# ch340_civ.net
KiCad netlist of a schematic drawn in EAGLE
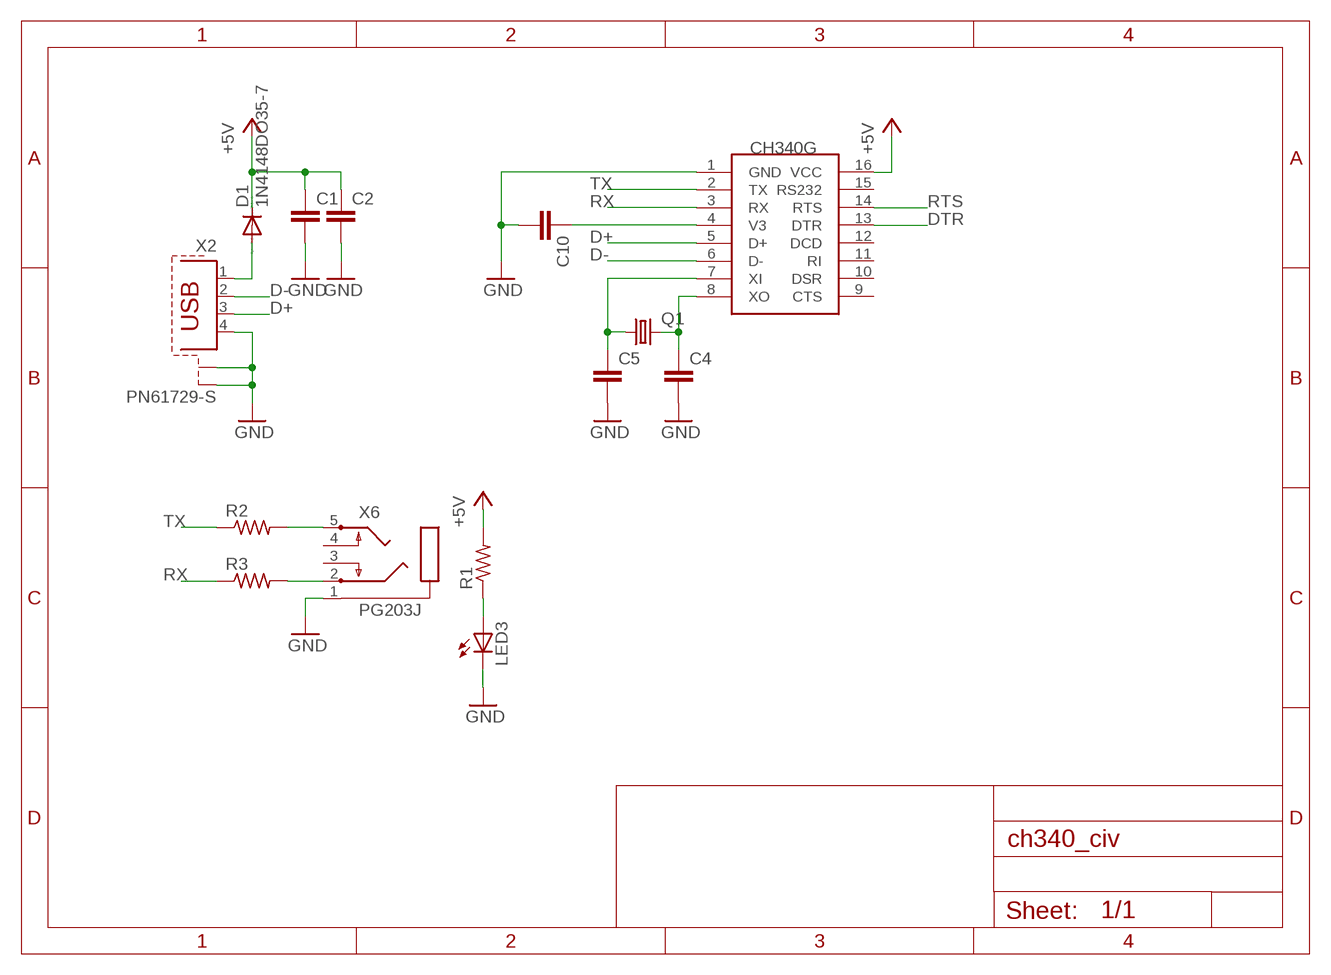
[diagram p0: schematic, sheet 1]

(export (version "E")
  (design (tool "Eeschema 10.0.6"))
  (components
    (comp (ref "C1")
      (value "C-EUC0805K")
      (footprint "eagle-import:C0805K")
      (libsource (lib "eagle-import") (part "C-EUC0805K"))
    )
    (comp (ref "C2")
      (value "C-EUC0805K")
      (footprint "eagle-import:C0805K")
      (libsource (lib "eagle-import") (part "C-EUC0805K"))
    )
    (comp (ref "C4")
      (value "C-EUC0805K")
      (footprint "eagle-import:C0805K")
      (libsource (lib "eagle-import") (part "C-EUC0805K"))
    )
    (comp (ref "C5")
      (value "C-EUC0805K")
      (footprint "eagle-import:C0805K")
      (libsource (lib "eagle-import") (part "C-EUC0805K"))
    )
    (comp (ref "C10")
      (value "C-EUC0805K")
      (footprint "eagle-import:C0805K")
      (libsource (lib "eagle-import") (part "C-EUC0805K"))
    )
    (comp (ref "D1")
      (value "1N4148DO35-7")
      (footprint "eagle-import:DO35-7")
      (libsource (lib "eagle-import") (part "1N4148DO35-7"))
    )
    (comp (ref "LED3")
      (value "LED3MM")
      (footprint "eagle-import:LED3MM")
      (libsource (lib "eagle-import") (part "LED3MM"))
    )
    (comp (ref "Q1")
      (value "CRYSTALHC49S")
      (footprint "eagle-import:HC49_S")
      (libsource (lib "eagle-import") (part "CRYSTALHC49S"))
    )
    (comp (ref "R1")
      (value "R-US_R0805")
      (footprint "eagle-import:R0805")
      (libsource (lib "eagle-import") (part "R-US_R0805"))
    )
    (comp (ref "R2")
      (value "R-US_M0805")
      (footprint "eagle-import:M0805")
      (libsource (lib "eagle-import") (part "R-US_M0805"))
    )
    (comp (ref "R3")
      (value "R-US_M0805")
      (footprint "eagle-import:M0805")
      (libsource (lib "eagle-import") (part "R-US_M0805"))
    )
    (comp (ref "U$1")
      (value "CH340G")
      (footprint "eagle-import:SOIC16")
      (libsource (lib "eagle-import") (part "CH340G"))
    )
    (comp (ref "X2")
      (value "PN61729-S")
      (footprint "eagle-import:PN61729-S")
      (libsource (lib "eagle-import") (part "PN61729-S"))
    )
    (comp (ref "X6")
      (value "PG203J")
      (footprint "eagle-import:PG203J")
      (libsource (lib "eagle-import") (part "PG203J"))
    )
  )
  (nets
    (net (code "1") (name "+5V") (class "Default")
      (node (ref "C1") (pin "1") (pinfunction "1_1") (pintype "passive"))
      (node (ref "C2") (pin "1") (pinfunction "1_1") (pintype "passive"))
      (node (ref "D1") (pin "C") (pinfunction "C_C") (pintype "passive"))
      (node (ref "R1") (pin "2") (pinfunction "2_2") (pintype "passive"))
      (node (ref "U$1") (pin "16") (pinfunction "VCC_16") (pintype "bidirectional"))
    )
    (net (code "2") (name "/D+") (class "Default")
      (node (ref "U$1") (pin "5") (pinfunction "D+_5") (pintype "bidirectional"))
      (node (ref "X2") (pin "3") (pinfunction "3_3") (pintype "passive"))
    )
    (net (code "3") (name "/D-") (class "Default")
      (node (ref "U$1") (pin "6") (pinfunction "D-_6") (pintype "bidirectional"))
      (node (ref "X2") (pin "2") (pinfunction "2_2") (pintype "passive"))
    )
    (net (code "4") (name "/DTR") (class "Default")
      (node (ref "U$1") (pin "13") (pinfunction "DTR_13") (pintype "bidirectional"))
    )
    (net (code "5") (name "/RTS") (class "Default")
      (node (ref "U$1") (pin "14") (pinfunction "RTS_14") (pintype "bidirectional"))
    )
    (net (code "6") (name "/RX") (class "Default")
      (node (ref "R3") (pin "1") (pinfunction "1_1") (pintype "passive"))
      (node (ref "U$1") (pin "3") (pinfunction "RX_3") (pintype "bidirectional"))
    )
    (net (code "7") (name "/TX") (class "Default")
      (node (ref "R2") (pin "1") (pinfunction "1_1") (pintype "passive"))
      (node (ref "U$1") (pin "2") (pinfunction "TX_2") (pintype "bidirectional"))
    )
    (net (code "8") (name "GND") (class "Default")
      (node (ref "C1") (pin "2") (pinfunction "2_2") (pintype "passive"))
      (node (ref "C10") (pin "2") (pinfunction "2_2") (pintype "passive"))
      (node (ref "C2") (pin "2") (pinfunction "2_2") (pintype "passive"))
      (node (ref "C4") (pin "2") (pinfunction "2_2") (pintype "passive"))
      (node (ref "C5") (pin "2") (pinfunction "2_2") (pintype "passive"))
      (node (ref "LED3") (pin "K") (pinfunction "C_K") (pintype "passive"))
      (node (ref "U$1") (pin "1") (pinfunction "GND_1") (pintype "bidirectional"))
      (node (ref "X2") (pin "4") (pinfunction "4_4") (pintype "passive"))
      (node (ref "X2") (pin "S1") (pinfunction "S1_S1") (pintype "passive"))
      (node (ref "X2") (pin "S2") (pinfunction "S2_S2") (pintype "passive"))
      (node (ref "X6") (pin "1") (pinfunction "1_1") (pintype "passive"))
    )
    (net (code "9") (name "Net-(D1-PadA)") (class "Default")
      (node (ref "D1") (pin "A") (pinfunction "A_A") (pintype "passive"))
      (node (ref "X2") (pin "1") (pinfunction "1_1") (pintype "passive"))
    )
    (net (code "10") (name "Net-(LED3-PadA)") (class "Default")
      (node (ref "LED3") (pin "A") (pinfunction "A_A") (pintype "passive"))
      (node (ref "R1") (pin "1") (pinfunction "1_1") (pintype "passive"))
    )
    (net (code "11") (name "Net-(R2-Pad2)") (class "Default")
      (node (ref "R2") (pin "2") (pinfunction "2_2") (pintype "passive"))
      (node (ref "X6") (pin "5") (pinfunction "5_5") (pintype "passive"))
    )
    (net (code "12") (name "Net-(R3-Pad2)") (class "Default")
      (node (ref "R3") (pin "2") (pinfunction "2_2") (pintype "passive"))
      (node (ref "X6") (pin "2") (pinfunction "2_2") (pintype "passive"))
    )
    (net (code "13") (name "Net-(U$1-V3)") (class "Default")
      (node (ref "C10") (pin "1") (pinfunction "1_1") (pintype "passive"))
      (node (ref "U$1") (pin "4") (pinfunction "V3_4") (pintype "bidirectional"))
    )
    (net (code "14") (name "Net-(U$1-XI)") (class "Default")
      (node (ref "C5") (pin "1") (pinfunction "1_1") (pintype "passive"))
      (node (ref "Q1") (pin "1") (pinfunction "1_1") (pintype "passive"))
      (node (ref "U$1") (pin "7") (pinfunction "XI_7") (pintype "bidirectional"))
    )
    (net (code "15") (name "Net-(U$1-XO)") (class "Default")
      (node (ref "C4") (pin "1") (pinfunction "1_1") (pintype "passive"))
      (node (ref "Q1") (pin "2") (pinfunction "2_2") (pintype "passive"))
      (node (ref "U$1") (pin "8") (pinfunction "XO_8") (pintype "bidirectional"))
    )
    (net (code "16") (name "unconnected-(U$1-CTS-Pad9)") (class "Default")
      (node (ref "U$1") (pin "9") (pinfunction "CTS_9") (pintype "bidirectional"))
    )
    (net (code "17") (name "unconnected-(U$1-DCD-Pad12)") (class "Default")
      (node (ref "U$1") (pin "12") (pinfunction "DCD_12") (pintype "bidirectional"))
    )
    (net (code "18") (name "unconnected-(U$1-DSR-Pad10)") (class "Default")
      (node (ref "U$1") (pin "10") (pinfunction "DSR_10") (pintype "bidirectional"))
    )
    (net (code "19") (name "unconnected-(U$1-RI-Pad11)") (class "Default")
      (node (ref "U$1") (pin "11") (pinfunction "RI_11") (pintype "bidirectional"))
    )
    (net (code "20") (name "unconnected-(U$1-RS232-Pad15)") (class "Default")
      (node (ref "U$1") (pin "15") (pinfunction "RS232_15") (pintype "bidirectional"))
    )
    (net (code "21") (name "unconnected-(X6-Pad3)") (class "Default")
      (node (ref "X6") (pin "3") (pinfunction "3_3") (pintype "passive"))
    )
    (net (code "22") (name "unconnected-(X6-Pad4)") (class "Default")
      (node (ref "X6") (pin "4") (pinfunction "4_4") (pintype "passive"))
    )
  )
)
